# 24V_Main_Regulator.net
KiCad netlist of a schematic drawn in Altium Designer
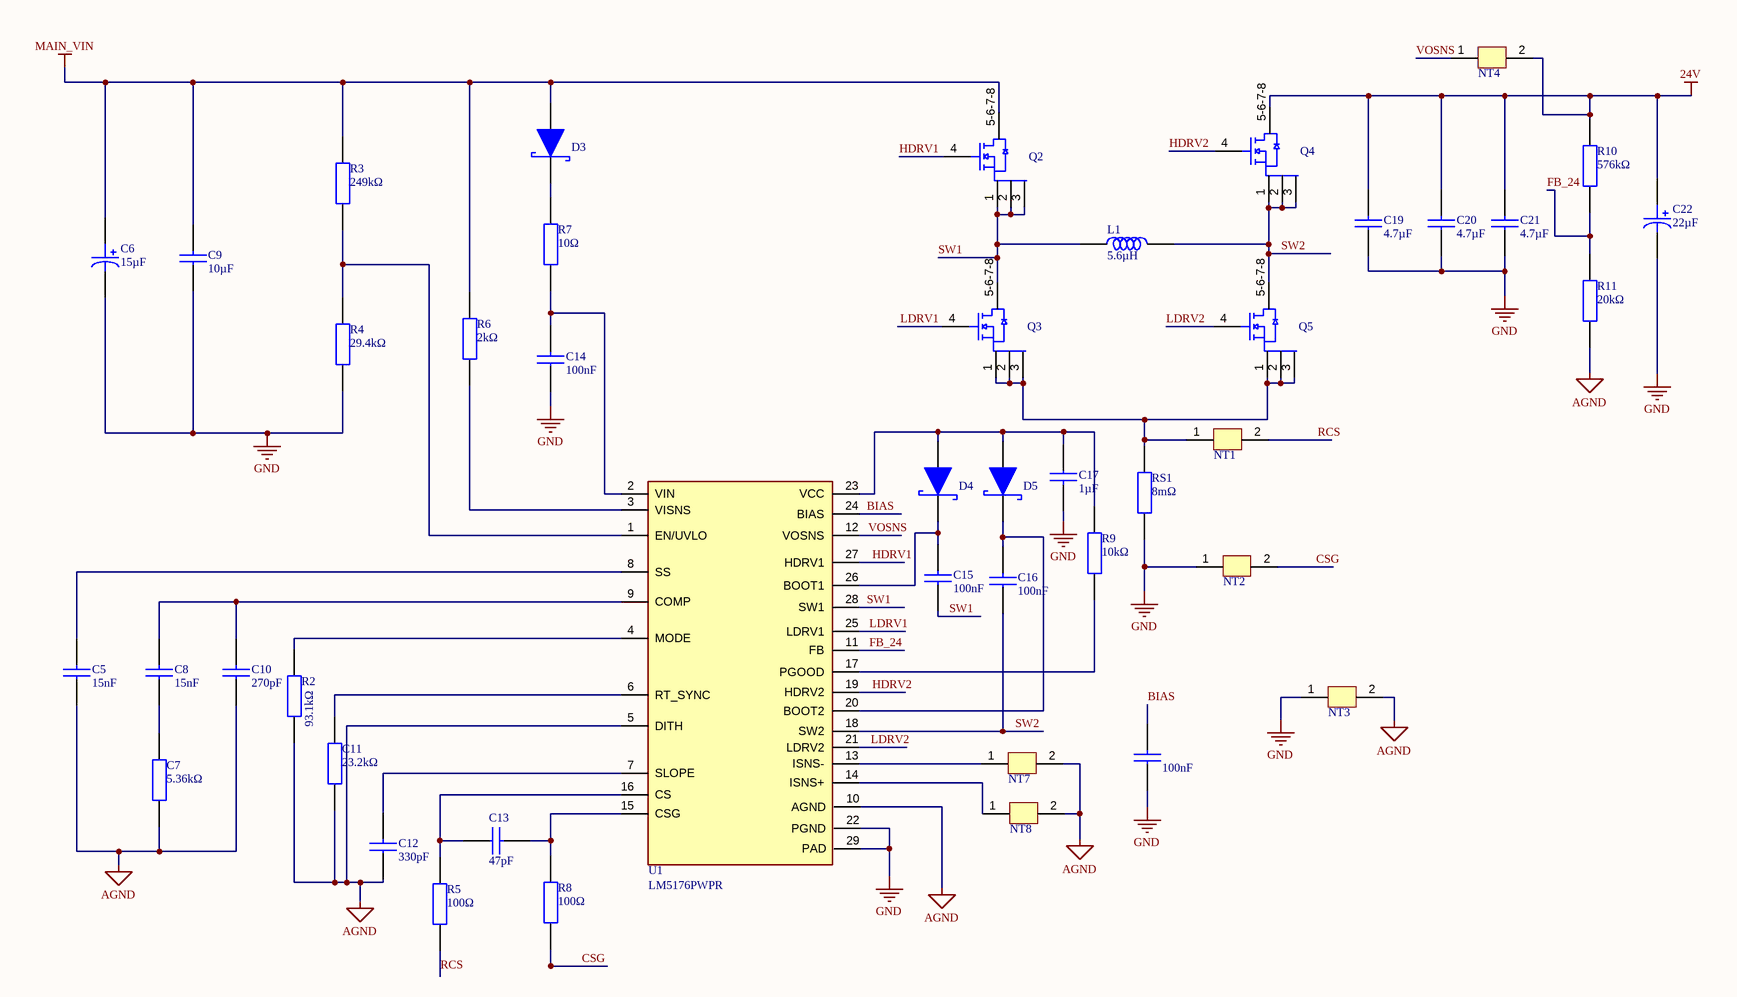
[diagram p0: 24V_Main_Regulator.SchDoc]

(export (version "E")
  (design (tool "Eeschema 10.0.6"))
  (components
    (comp (ref "C5")
      (value "15nF")
      (footprint "CAP_0603")
      (description "0603 C 15NF Ceramic Multilayer Capacitor, 25 V, +125DEGC, C0G Dielectric, +/-5%")
      (fields
        (field (name "MANUFACTURER") "Yageo Group")
        (field (name "MANUFACTURER PART NUMBER") "C0603C153J3GACTU")
      )
      (libsource (lib "PDU_BOM") (part "C0603C153J3GACTU"))
    )
    (comp (ref "C6")
      (value "15µF")
      (footprint "CAP ALUM SMD")
      (description "Cap Aluminum 15uF 100V 20% (8 X 11.9mm) Cylindrical 0.04 Ohm 2350mA 5000 hr 105°C T/R")
      (fields (field (name "MANUFACTURER") "Panasonic") (field (name "MANUFACTURER PART NUMBER") "100SXV15M"))
      (libsource (lib "PDU_BOM") (part "100SXV15M"))
    )
    (comp (ref "C7")
      (value "5.36kΩ")
      (footprint "RES_0402")
      (description "Res Thick Film 0402 5.36K Ohm 1% 0.063W(1/16W) ±100ppm/C Pad SMD T/R Automotive AEC-Q200")
      (fields
        (field (name "MANUFACTURER") "Vishay")
        (field (name "MANUFACTURER PART NUMBER") "CRCW04025K36FKED")
      )
      (libsource (lib "PDU_BOM") (part "CRCW04025K36FKED"))
    )
    (comp (ref "C8")
      (value "15nF")
      (footprint "CAP_0402")
      (description "Cap Ceramic 0.015uF 50V X7R 10% Pad SMD 0402 125C Low ESR Automotive T/R")
      (fields
        (field (name "MANUFACTURER") "TDK")
        (field (name "MANUFACTURER PART NUMBER") "CGA2B3X7R1H153K050BB")
      )
      (libsource (lib "PDU_BOM") (part "CGA2B3X7R1H153K050BB"))
    )
    (comp (ref "C9")
      (value "10µF")
      (footprint "CAP_2220")
      (description "Multilayer Ceramic Capacitor, C Series, 10 - F, - 20%, X7S, 100 V, 2220 [5650 Metric]")
      (fields
        (field (name "MANUFACTURER") "TDK")
        (field (name "MANUFACTURER PART NUMBER") "C5750X7S2A106M230KB")
      )
      (libsource (lib "PDU_BOM") (part "C5750X7S2A106M230KB"))
    )
    (comp (ref "C10")
      (value "270pF")
      (footprint "CAP_0805")
      (description "50V 270pF C0G 卤5% 0805 Multilayer Ceramic Capacitors MLCC - SMD/SMT ROHS")
      (fields
        (field (name "MANUFACTURER") "Samsung Electro-Mechanics")
        (field (name "MANUFACTURER PART NUMBER") "CL21C271JBANNNC")
      )
      (libsource (lib "PDU_BOM") (part "CL21C271JBANNNC"))
    )
    (comp (ref "C11")
      (value "23.2kΩ")
      (footprint "RES_0402")
      (description "Res Thick Film 0402 23.2K Ohm 1% 1/16W ±100ppm/°C Molded SMD Paper T/R")
      (fields
        (field (name "MANUFACTURER") "Vishay")
        (field (name "MANUFACTURER PART NUMBER") "CRCW040223K2FKED")
      )
      (libsource (lib "PDU_BOM") (part "CRCW040223K2FKED"))
    )
    (comp (ref "C12")
      (value "330pF")
      (footprint "CAP_0603")
      (description "50V 330pF C0G 卤5% 0603 Multilayer Ceramic Capacitors MLCC - SMD/SMT ROHS")
      (fields
        (field (name "MANUFACTURER") "Samsung Electro-Mechanics")
        (field (name "MANUFACTURER PART NUMBER") "CL10C331JB8NNNC")
      )
      (libsource (lib "PDU_BOM") (part "CL10C331JB8NNNC"))
    )
    (comp (ref "C13")
      (value "47pF")
      (footprint "CAP_0603")
      (description "50V 47pF C0G ±5% 0603 Multilayer Ceramic Capacitors MLCC - SMD/SMT ROHS")
      (fields
        (field (name "MANUFACTURER") "KYOCERA AVX")
        (field (name "MANUFACTURER PART NUMBER") "06035A470JAT2A")
      )
      (libsource (lib "PDU_BOM") (part "06035A470JAT2A"))
    )
    (comp (ref "C14")
      (value "100nF")
      (footprint "CAP_0603")
      (description "Multilayer Ceramic Capacitor, CC Series, 0.1 - F, - 10%, X7R, 50 V, 0603 [1608 Metric]")
      (fields
        (field (name "MANUFACTURER") "Yageo Group")
        (field (name "MANUFACTURER PART NUMBER") "CC0603KRX7R9BB104")
      )
      (libsource (lib "PDU_BOM") (part "CC0603KRX7R9BB104"))
    )
    (comp (ref "C15")
      (value "100nF")
      (footprint "CAP_0603")
      (description "0603 100 nF 25 V ±10% Tolerance X7R Surface Mount Multilayer Ceramic Capacitor")
      (fields
        (field (name "MANUFACTURER") "KYOCERA AVX")
        (field (name "MANUFACTURER PART NUMBER") "06033C104KAT2A")
      )
      (libsource (lib "PDU_BOM") (part "06033C104KAT2A"))
    )
    (comp (ref "C16")
      (value "100nF")
      (footprint "CAP_0603")
      (description "0603 100 nF 25 V ±10% Tolerance X7R Surface Mount Multilayer Ceramic Capacitor")
      (fields
        (field (name "MANUFACTURER") "KYOCERA AVX")
        (field (name "MANUFACTURER PART NUMBER") "06033C104KAT2A")
      )
      (libsource (lib "PDU_BOM") (part "06033C104KAT2A"))
    )
    (comp (ref "C17")
      (value "1µF")
      (footprint "CAP_0603")
      (description "16V 1uF X7R ±10% 0603 Multilayer Ceramic Capacitors MLCC - SMD/SMT ROHS")
      (fields
        (field (name "MANUFACTURER") "TAIYO YUDEN")
        (field (name "MANUFACTURER PART NUMBER") "EMK107B7105KA-T")
      )
      (libsource (lib "PDU_BOM") (part "EMK107B7105KA-T"))
    )
    (comp (ref "C18")
      (value "100nF")
      (footprint "CAP_0805")
      (description "50V 100nF X7R ±20% 0805 Multilayer Ceramic Capacitors MLCC - SMD/SMT ROHS")
      (fields
        (field (name "MANUFACTURER") "Yageo Group")
        (field (name "MANUFACTURER PART NUMBER") "C0805C104M5RACTU")
      )
      (libsource (lib "PDU_BOM") (part "C0805C104M5RACTU"))
    )
    (comp (ref "C19")
      (value "4.7µF")
      (footprint "CAP_0805")
      (fields
        (field (name "MANUFACTURER") "TAIYO YUDEN")
        (field (name "MANUFACTURER PART NUMBER") "MSASU21GBB5475KTNA01")
      )
      (libsource (lib "PDU_BOM") (part "MSASU21GBB5475KTNA01"))
    )
    (comp (ref "C20")
      (value "4.7µF")
      (footprint "CAP_0805")
      (fields
        (field (name "MANUFACTURER") "TAIYO YUDEN")
        (field (name "MANUFACTURER PART NUMBER") "MSASU21GBB5475KTNA01")
      )
      (libsource (lib "PDU_BOM") (part "MSASU21GBB5475KTNA01"))
    )
    (comp (ref "C21")
      (value "4.7µF")
      (footprint "CAP_0805")
      (fields
        (field (name "MANUFACTURER") "TAIYO YUDEN")
        (field (name "MANUFACTURER PART NUMBER") "MSASU21GBB5475KTNA01")
      )
      (libsource (lib "PDU_BOM") (part "MSASU21GBB5475KTNA01"))
    )
    (comp (ref "C22")
      (value "22µF")
      (footprint "CAP ALUM SMD")
      (description "Capacitor, Aluminum Electrolytic, Solid Polymer, Polarized, 35V, 22Uf, Surface Mount, 2626")
      (fields (field (name "MANUFACTURER") "Panasonic") (field (name "MANUFACTURER PART NUMBER") "35SVPF22M"))
      (libsource (lib "PDU_BOM") (part "35SVPF22M"))
    )
    (comp (ref "D3")
      (value "SS110")
      (footprint "SS110")
      (description "Rectifier Diode, Schottky, 1 Phase, 1 Element, 1A, 100V V(RRM), Silicon")
      (fields (field (name "MANUFACTURER") "Taiwan Semiconductor"))
      (libsource (lib "PDU_BOM") (part "SS110"))
    )
    (comp (ref "D4")
      (value "SS110")
      (footprint "SS110")
      (description "Rectifier Diode, Schottky, 1 Phase, 1 Element, 1A, 100V V(RRM), Silicon")
      (fields (field (name "MANUFACTURER") "Taiwan Semiconductor"))
      (libsource (lib "PDU_BOM") (part "SS110"))
    )
    (comp (ref "D5")
      (value "SS110")
      (footprint "SS110")
      (description "Rectifier Diode, Schottky, 1 Phase, 1 Element, 1A, 100V V(RRM), Silicon")
      (fields (field (name "MANUFACTURER") "Taiwan Semiconductor"))
      (libsource (lib "PDU_BOM") (part "SS110"))
    )
    (comp (ref "L1")
      (value "5.6µH")
      (footprint "XAL1010")
      (description "General Purpose Inductor, 5.6uH, 20%, 1 Element, Composite-Core, SMD, 4539")
      (fields
        (field (name "MANUFACTURER") "Coilcraft")
        (field (name "MANUFACTURER PART NUMBER") "XAL1010-562MEB")
      )
      (libsource (lib "PDU_BOM") (part "XAL1010-562MEB"))
    )
    (comp (ref "NT1") (value "Net-Tie") (footprint "Net-Tie") (libsource (lib "PDU_BOM") (part "Net-Tie")))
    (comp (ref "NT2") (value "Net-Tie") (footprint "Net-Tie") (libsource (lib "PDU_BOM") (part "Net-Tie")))
    (comp (ref "NT3") (value "Net-Tie") (footprint "Net-Tie") (libsource (lib "PDU_BOM") (part "Net-Tie")))
    (comp (ref "NT4") (value "Net-Tie") (footprint "Net-Tie") (libsource (lib "PDU_BOM") (part "Net-Tie")))
    (comp (ref "NT7") (value "Net-Tie") (footprint "Net-Tie") (libsource (lib "PDU_BOM") (part "Net-Tie")))
    (comp (ref "NT8") (value "Net-Tie") (footprint "Net-Tie") (libsource (lib "PDU_BOM") (part "Net-Tie")))
    (comp (ref "Q2")
      (value "CSD19534Q5A")
      (footprint "SON 5X6")
      (description "100-V, N channel NexFET™ power MOSFET, single SON 5 mm x 6 mm, 15.1 mOhm 8-VSONP -55 to 150")
      (fields (field (name "MANUFACTURER") "Texas Instruments"))
      (libsource (lib "PDU_BOM") (part "CSD19534Q5A"))
    )
    (comp (ref "Q3")
      (value "CSD19534Q5A")
      (footprint "SON 5X6")
      (description "100-V, N channel NexFET™ power MOSFET, single SON 5 mm x 6 mm, 15.1 mOhm 8-VSONP -55 to 150")
      (fields (field (name "MANUFACTURER") "Texas Instruments"))
      (libsource (lib "PDU_BOM") (part "CSD19534Q5A"))
    )
    (comp (ref "Q4")
      (value "CSD18540Q5B")
      (footprint "SON 5X6")
      (description "60-V, N channel NexFET™ power MOSFET, single SON 5 mm x 6 mm, 2.2 mOhm 8-VSON-CLIP -55 to 175")
      (fields (field (name "MANUFACTURER") "Texas Instruments"))
      (libsource (lib "PDU_BOM") (part "CSD18540Q5B"))
    )
    (comp (ref "Q5")
      (value "CSD18531Q5A")
      (footprint "SON 5X6")
      (description "60-V, N channel NexFET™ power MOSFET, single SON 5 mm x 6 mm, 4.6 mOhm 8-VSONP -55 to 150")
      (fields
        (field (name "MANUFACTURER") "Texas Instruments")
        (field (name "MANUFACTURER PART NUMBER") "CSD18531Q5AT")
      )
      (libsource (lib "PDU_BOM") (part "CSD18531Q5A"))
    )
    (comp (ref "R2")
      (value "93.1kΩ")
      (footprint "RES_0603")
      (description "Res Thick Film 0603 93.1K Ohm 1% 0.1W(1/10W) ±100ppm/C Pad SMD T/R")
      (fields
        (field (name "MANUFACTURER") "Yageo Group")
        (field (name "MANUFACTURER PART NUMBER") "RC0603FR-0793K1L")
      )
      (libsource (lib "PDU_BOM") (part "RC0603FR-0793K1L"))
    )
    (comp (ref "R3")
      (value "249kΩ")
      (footprint "RES_0402")
      (description "Fixed Resistor, Metal Glaze/Thick Film, 0.063W, 249000ohm, 50V, 1% +/-Tol, Surface Mount, 0402")
      (fields
        (field (name "MANUFACTURER") "Vishay")
        (field (name "MANUFACTURER PART NUMBER") "CRCW0402249KFKED")
      )
      (libsource (lib "PDU_BOM") (part "CRCW0402249KFKED"))
    )
    (comp (ref "R4")
      (value "29.4kΩ")
      (footprint "RES_0402")
      (description "Res Thick Film 0402 29.4K Ohm 1% 0.063W(1/16W) ±100ppm/C Pad SMD T/R Automotive AEC-Q200")
      (fields
        (field (name "MANUFACTURER") "Vishay")
        (field (name "MANUFACTURER PART NUMBER") "CRCW040229K4FKED")
      )
      (libsource (lib "PDU_BOM") (part "CRCW040229K4FKED"))
    )
    (comp (ref "R5")
      (value "100Ω")
      (footprint "RES_0603")
      (description "Res Thick Film 0603 100 Ohm 1% 0.1W(1/10W) ±100ppm/°C Pad SMD T/R Automotive AEC-Q200")
      (fields
        (field (name "MANUFACTURER") "Vishay")
        (field (name "MANUFACTURER PART NUMBER") "CRCW0603100RFKEA")
      )
      (libsource (lib "PDU_BOM") (part "CRCW0603100RFKEA"))
    )
    (comp (ref "R6")
      (value "2kΩ")
      (footprint "RES_0603")
      (description "100mW Thick Film Resistors 100V ±1% ±100ppm/℃ 2kΩ 0603 Chip Resistor - Surface Mount ROHS")
      (fields
        (field (name "MANUFACTURER") "Vishay")
        (field (name "MANUFACTURER PART NUMBER") "CRCW06032K00FKEA")
      )
      (libsource (lib "PDU_BOM") (part "CRCW06032K00FKEA"))
    )
    (comp (ref "R7")
      (value "10Ω")
      (footprint "RES_0603")
      (description "Res Thick Film 0603 10 Ohm 1% 0.1W(1/10W) ±200ppm/C Pad SMD T/R")
      (fields
        (field (name "MANUFACTURER") "Yageo Group")
        (field (name "MANUFACTURER PART NUMBER") "RC0603FR-0710RL")
      )
      (libsource (lib "PDU_BOM") (part "RC0603FR-0710RL"))
    )
    (comp (ref "R8")
      (value "100Ω")
      (footprint "RES_0603")
      (description "Res Thick Film 0603 100 Ohm 1% 0.1W(1/10W) ±100ppm/°C Pad SMD T/R Automotive AEC-Q200")
      (fields
        (field (name "MANUFACTURER") "Vishay")
        (field (name "MANUFACTURER PART NUMBER") "CRCW0603100RFKEA")
      )
      (libsource (lib "PDU_BOM") (part "CRCW0603100RFKEA"))
    )
    (comp (ref "R9")
      (value "10kΩ")
      (footprint "RES_0603")
      (description "100mW Thick Film Resistors 75V ±100ppm/℃ ±1% 10kΩ 0603 Chip Resistor - Surface Mount ROHS")
      (fields
        (field (name "MANUFACTURER") "Yageo Group")
        (field (name "MANUFACTURER PART NUMBER") "RC0603FR-0710KL")
      )
      (libsource (lib "PDU_BOM") (part "RC0603FR-0710KL"))
    )
    (comp (ref "R10")
      (value "576kΩ")
      (footprint "RES_0603")
      (description "Res Thick Film 0603 576K Ohm 1% 0.1W(1/10W) ±100ppm/C Pad SMD T/R")
      (fields
        (field (name "MANUFACTURER") "Yageo Group")
        (field (name "MANUFACTURER PART NUMBER") "RC0603FR-07576KL")
      )
      (libsource (lib "PDU_BOM") (part "RC0603FR-07576KL"))
    )
    (comp (ref "R11")
      (value "20kΩ")
      (footprint "RES_0603")
      (description "100mW Thick Film Resistors 75V ±100ppm/℃ ±1% 20kΩ 0603 Chip Resistor - Surface Mount ROHS")
      (fields
        (field (name "MANUFACTURER") "Yageo Group")
        (field (name "MANUFACTURER PART NUMBER") "RC0603FR-0720KL")
      )
      (libsource (lib "PDU_BOM") (part "RC0603FR-0720KL"))
    )
    (comp (ref "RS1")
      (value "8mΩ")
      (footprint "RES_2512")
      (description "Res Current Sense Thick Film 2512 8m Ohm 1% 2W Molded Emboss T/R")
      (fields
        (field (name "MANUFACTURER") "ROHM")
        (field (name "MANUFACTURER PART NUMBER") "PMR100HZPFU8L00")
      )
      (libsource (lib "PDU_BOM") (part "PMR100HZPFU8L00"))
    )
    (comp (ref "U1")
      (value "LM5176PWPR")
      (footprint "28-HTSSOP")
      (description "55V wide VIN synchronous 4-switch buck-boost controller 28-HTSSOP -40 to 125")
      (fields (field (name "MANUFACTURER") "Texas Instruments"))
      (libsource (lib "PDU_BOM") (part "LM5176PWPR"))
    )
  )
  (nets
    (net (code "1") (name "/BIAS") (class "Default")
      (node (ref "C18") (pin "2") (pinfunction "2_2") (pintype "passive"))
      (node (ref "U1") (pin "24") (pinfunction "BIAS_24") (pintype "passive"))
    )
    (net (code "2") (name "/CSG") (class "Default")
      (node (ref "NT2") (pin "2") (pinfunction "2_2") (pintype "passive"))
      (node (ref "R8") (pin "1") (pinfunction "1_1") (pintype "passive"))
    )
    (net (code "3") (name "/FB_24") (class "Default")
      (node (ref "R10") (pin "1") (pinfunction "1_1") (pintype "passive"))
      (node (ref "R11") (pin "2") (pinfunction "2_2") (pintype "passive"))
      (node (ref "U1") (pin "11") (pinfunction "FB_11") (pintype "passive"))
    )
    (net (code "4") (name "/HDRV1") (class "Default")
      (node (ref "Q2") (pin "4") (pinfunction "G_4") (pintype "passive"))
      (node (ref "U1") (pin "27") (pinfunction "HDRV1_27") (pintype "passive"))
    )
    (net (code "5") (name "/HDRV2") (class "Default")
      (node (ref "Q4") (pin "4") (pinfunction "G_4") (pintype "passive"))
      (node (ref "U1") (pin "19") (pinfunction "HDRV2_19") (pintype "passive"))
    )
    (net (code "6") (name "/LDRV1") (class "Default")
      (node (ref "Q3") (pin "4") (pinfunction "G_4") (pintype "passive"))
      (node (ref "U1") (pin "25") (pinfunction "LDRV1_25") (pintype "passive"))
    )
    (net (code "7") (name "/LDRV2") (class "Default")
      (node (ref "Q5") (pin "4") (pinfunction "G_4") (pintype "passive"))
      (node (ref "U1") (pin "21") (pinfunction "LDRV2_21") (pintype "passive"))
    )
    (net (code "8") (name "/RCS") (class "Default")
      (node (ref "NT1") (pin "2") (pinfunction "2_2") (pintype "passive"))
      (node (ref "R5") (pin "1") (pinfunction "1_1") (pintype "passive"))
    )
    (net (code "9") (name "/SW1") (class "Default")
      (node (ref "C15") (pin "1") (pinfunction "1_1") (pintype "passive"))
      (node (ref "L1") (pin "1") (pinfunction "1_1") (pintype "passive"))
      (node (ref "Q2") (pin "1") (pinfunction "S_1") (pintype "passive"))
      (node (ref "Q2") (pin "2") (pinfunction "S_2") (pintype "passive"))
      (node (ref "Q2") (pin "3") (pinfunction "S_3") (pintype "passive"))
      (node (ref "Q3") (pin "5-6-7-8") (pinfunction "D_5-6-7-8") (pintype "passive"))
      (node (ref "U1") (pin "28") (pinfunction "SW1_28") (pintype "passive"))
    )
    (net (code "10") (name "/SW2") (class "Default")
      (node (ref "C16") (pin "1") (pinfunction "1_1") (pintype "passive"))
      (node (ref "L1") (pin "2") (pinfunction "2_2") (pintype "passive"))
      (node (ref "Q4") (pin "1") (pinfunction "S_1") (pintype "passive"))
      (node (ref "Q4") (pin "2") (pinfunction "S_2") (pintype "passive"))
      (node (ref "Q4") (pin "3") (pinfunction "S_3") (pintype "passive"))
      (node (ref "Q5") (pin "5-6-7-8") (pinfunction "D_5-6-7-8") (pintype "passive"))
      (node (ref "U1") (pin "18") (pinfunction "SW2_18") (pintype "passive"))
    )
    (net (code "11") (name "/VOSNS") (class "Default")
      (node (ref "NT4") (pin "1") (pinfunction "1_1") (pintype "passive"))
      (node (ref "U1") (pin "12") (pinfunction "VOSNS_12") (pintype "passive"))
    )
    (net (code "12") (name "24V") (class "Default")
      (node (ref "C19") (pin "2") (pinfunction "2_2") (pintype "passive"))
      (node (ref "C20") (pin "2") (pinfunction "2_2") (pintype "passive"))
      (node (ref "C21") (pin "2") (pinfunction "2_2") (pintype "passive"))
      (node (ref "C22") (pin "1") (pinfunction "C_1") (pintype "passive"))
      (node (ref "NT4") (pin "2") (pinfunction "2_2") (pintype "passive"))
      (node (ref "Q4") (pin "5-6-7-8") (pinfunction "D_5-6-7-8") (pintype "passive"))
      (node (ref "R10") (pin "2") (pinfunction "2_2") (pintype "passive"))
    )
    (net (code "13") (name "AGND") (class "Default")
      (node (ref "C10") (pin "1") (pinfunction "1_1") (pintype "passive"))
      (node (ref "C11") (pin "1") (pinfunction "1_1") (pintype "passive"))
      (node (ref "C12") (pin "1") (pinfunction "1_1") (pintype "passive"))
      (node (ref "C5") (pin "1") (pinfunction "1_1") (pintype "passive"))
      (node (ref "C7") (pin "1") (pinfunction "1_1") (pintype "passive"))
      (node (ref "NT3") (pin "2") (pinfunction "2_2") (pintype "passive"))
      (node (ref "NT7") (pin "2") (pinfunction "2_2") (pintype "passive"))
      (node (ref "NT8") (pin "2") (pinfunction "2_2") (pintype "passive"))
      (node (ref "R11") (pin "1") (pinfunction "1_1") (pintype "passive"))
      (node (ref "R2") (pin "1") (pinfunction "1_1") (pintype "passive"))
      (node (ref "U1") (pin "10") (pinfunction "AGND_10") (pintype "passive"))
      (node (ref "U1") (pin "5") (pinfunction "DITH_5") (pintype "passive"))
    )
    (net (code "14") (name "GND") (class "Default")
      (node (ref "C14") (pin "1") (pinfunction "1_1") (pintype "passive"))
      (node (ref "C17") (pin "2") (pinfunction "2_2") (pintype "passive"))
      (node (ref "C18") (pin "1") (pinfunction "1_1") (pintype "passive"))
      (node (ref "C19") (pin "1") (pinfunction "1_1") (pintype "passive"))
      (node (ref "C20") (pin "1") (pinfunction "1_1") (pintype "passive"))
      (node (ref "C21") (pin "1") (pinfunction "1_1") (pintype "passive"))
      (node (ref "C22") (pin "2") (pinfunction "A_2") (pintype "passive"))
      (node (ref "C6") (pin "2") (pinfunction "A_2") (pintype "passive"))
      (node (ref "C9") (pin "1") (pinfunction "1_1") (pintype "passive"))
      (node (ref "NT2") (pin "1") (pinfunction "1_1") (pintype "passive"))
      (node (ref "NT3") (pin "1") (pinfunction "1_1") (pintype "passive"))
      (node (ref "R4") (pin "1") (pinfunction "1_1") (pintype "passive"))
      (node (ref "RS1") (pin "1") (pinfunction "1_1") (pintype "passive"))
      (node (ref "U1") (pin "22") (pinfunction "PGND_22") (pintype "passive"))
      (node (ref "U1") (pin "29") (pinfunction "PAD_29") (pintype "passive"))
    )
    (net (code "15") (name "MAIN_VIN") (class "Default")
      (node (ref "C6") (pin "1") (pinfunction "C_1") (pintype "passive"))
      (node (ref "C9") (pin "2") (pinfunction "2_2") (pintype "passive"))
      (node (ref "D3") (pin "2") (pinfunction "Anode_2") (pintype "power_in"))
      (node (ref "Q2") (pin "5-6-7-8") (pinfunction "D_5-6-7-8") (pintype "passive"))
      (node (ref "R3") (pin "2") (pinfunction "2_2") (pintype "passive"))
      (node (ref "R6") (pin "2") (pinfunction "2_2") (pintype "passive"))
    )
    (net (code "16") (name "Net-(C7-Pad2)") (class "Default")
      (node (ref "C7") (pin "2") (pinfunction "2_2") (pintype "passive"))
      (node (ref "C8") (pin "1") (pinfunction "1_1") (pintype "passive"))
    )
    (net (code "17") (name "Net-(D3-Cathode)") (class "Default")
      (node (ref "D3") (pin "1") (pinfunction "Cathode_1") (pintype "power_in"))
      (node (ref "R7") (pin "2") (pinfunction "2_2") (pintype "passive"))
    )
    (net (code "18") (name "Net-(D4-Anode)") (class "Default")
      (node (ref "C17") (pin "1") (pinfunction "1_1") (pintype "passive"))
      (node (ref "D4") (pin "2") (pinfunction "Anode_2") (pintype "power_in"))
      (node (ref "D5") (pin "2") (pinfunction "Anode_2") (pintype "power_in"))
      (node (ref "R9") (pin "2") (pinfunction "2_2") (pintype "passive"))
      (node (ref "U1") (pin "23") (pinfunction "VCC_23") (pintype "passive"))
    )
    (net (code "19") (name "Net-(D4-Cathode)") (class "Default")
      (node (ref "C15") (pin "2") (pinfunction "2_2") (pintype "passive"))
      (node (ref "D4") (pin "1") (pinfunction "Cathode_1") (pintype "power_in"))
      (node (ref "U1") (pin "26") (pinfunction "BOOT1_26") (pintype "passive"))
    )
    (net (code "20") (name "Net-(D5-Cathode)") (class "Default")
      (node (ref "C16") (pin "2") (pinfunction "2_2") (pintype "passive"))
      (node (ref "D5") (pin "1") (pinfunction "Cathode_1") (pintype "power_in"))
      (node (ref "U1") (pin "20") (pinfunction "BOOT2_20") (pintype "passive"))
    )
    (net (code "21") (name "Net-(NT1-Pad1)") (class "Default")
      (node (ref "NT1") (pin "1") (pinfunction "1_1") (pintype "passive"))
      (node (ref "Q3") (pin "1") (pinfunction "S_1") (pintype "passive"))
      (node (ref "Q3") (pin "2") (pinfunction "S_2") (pintype "passive"))
      (node (ref "Q3") (pin "3") (pinfunction "S_3") (pintype "passive"))
      (node (ref "Q5") (pin "1") (pinfunction "S_1") (pintype "passive"))
      (node (ref "Q5") (pin "2") (pinfunction "S_2") (pintype "passive"))
      (node (ref "Q5") (pin "3") (pinfunction "S_3") (pintype "passive"))
      (node (ref "RS1") (pin "2") (pinfunction "2_2") (pintype "passive"))
    )
    (net (code "22") (name "Net-(U1-COMP)") (class "Default")
      (node (ref "C10") (pin "2") (pinfunction "2_2") (pintype "passive"))
      (node (ref "C8") (pin "2") (pinfunction "2_2") (pintype "passive"))
      (node (ref "U1") (pin "9") (pinfunction "COMP_9") (pintype "passive"))
    )
    (net (code "23") (name "Net-(U1-CS)") (class "Default")
      (node (ref "C13") (pin "1") (pinfunction "1_1") (pintype "passive"))
      (node (ref "R5") (pin "2") (pinfunction "2_2") (pintype "passive"))
      (node (ref "U1") (pin "16") (pinfunction "CS_16") (pintype "passive"))
    )
    (net (code "24") (name "Net-(U1-CSG)") (class "Default")
      (node (ref "C13") (pin "2") (pinfunction "2_2") (pintype "passive"))
      (node (ref "R8") (pin "2") (pinfunction "2_2") (pintype "passive"))
      (node (ref "U1") (pin "15") (pinfunction "CSG_15") (pintype "passive"))
    )
    (net (code "25") (name "Net-(U1-EN{slash}UVLO)") (class "Default")
      (node (ref "R3") (pin "1") (pinfunction "1_1") (pintype "passive"))
      (node (ref "R4") (pin "2") (pinfunction "2_2") (pintype "passive"))
      (node (ref "U1") (pin "1") (pinfunction "EN/UVLO_1") (pintype "passive"))
    )
    (net (code "26") (name "Net-(U1-ISNS+)") (class "Default")
      (node (ref "NT8") (pin "1") (pinfunction "1_1") (pintype "passive"))
      (node (ref "U1") (pin "14") (pinfunction "ISNS+_14") (pintype "passive"))
    )
    (net (code "27") (name "Net-(U1-ISNS-)") (class "Default")
      (node (ref "NT7") (pin "1") (pinfunction "1_1") (pintype "passive"))
      (node (ref "U1") (pin "13") (pinfunction "ISNS-_13") (pintype "passive"))
    )
    (net (code "28") (name "Net-(U1-MODE)") (class "Default")
      (node (ref "R2") (pin "2") (pinfunction "2_2") (pintype "passive"))
      (node (ref "U1") (pin "4") (pinfunction "MODE_4") (pintype "passive"))
    )
    (net (code "29") (name "Net-(U1-PGOOD)") (class "Default")
      (node (ref "R9") (pin "1") (pinfunction "1_1") (pintype "passive"))
      (node (ref "U1") (pin "17") (pinfunction "PGOOD_17") (pintype "passive"))
    )
    (net (code "30") (name "Net-(U1-RT_SYNC)") (class "Default")
      (node (ref "C11") (pin "2") (pinfunction "2_2") (pintype "passive"))
      (node (ref "U1") (pin "6") (pinfunction "RT_SYNC_6") (pintype "passive"))
    )
    (net (code "31") (name "Net-(U1-SLOPE)") (class "Default")
      (node (ref "C12") (pin "2") (pinfunction "2_2") (pintype "passive"))
      (node (ref "U1") (pin "7") (pinfunction "SLOPE_7") (pintype "passive"))
    )
    (net (code "32") (name "Net-(U1-SS)") (class "Default")
      (node (ref "C5") (pin "2") (pinfunction "2_2") (pintype "passive"))
      (node (ref "U1") (pin "8") (pinfunction "SS_8") (pintype "passive"))
    )
    (net (code "33") (name "Net-(U1-VIN)") (class "Default")
      (node (ref "C14") (pin "2") (pinfunction "2_2") (pintype "passive"))
      (node (ref "R7") (pin "1") (pinfunction "1_1") (pintype "passive"))
      (node (ref "U1") (pin "2") (pinfunction "VIN_2") (pintype "passive"))
    )
    (net (code "34") (name "Net-(U1-VISNS)") (class "Default")
      (node (ref "R6") (pin "1") (pinfunction "1_1") (pintype "passive"))
      (node (ref "U1") (pin "3") (pinfunction "VISNS_3") (pintype "passive"))
    )
  )
)
